# Hank2.net
KiCad netlist of a schematic drawn in EAGLE
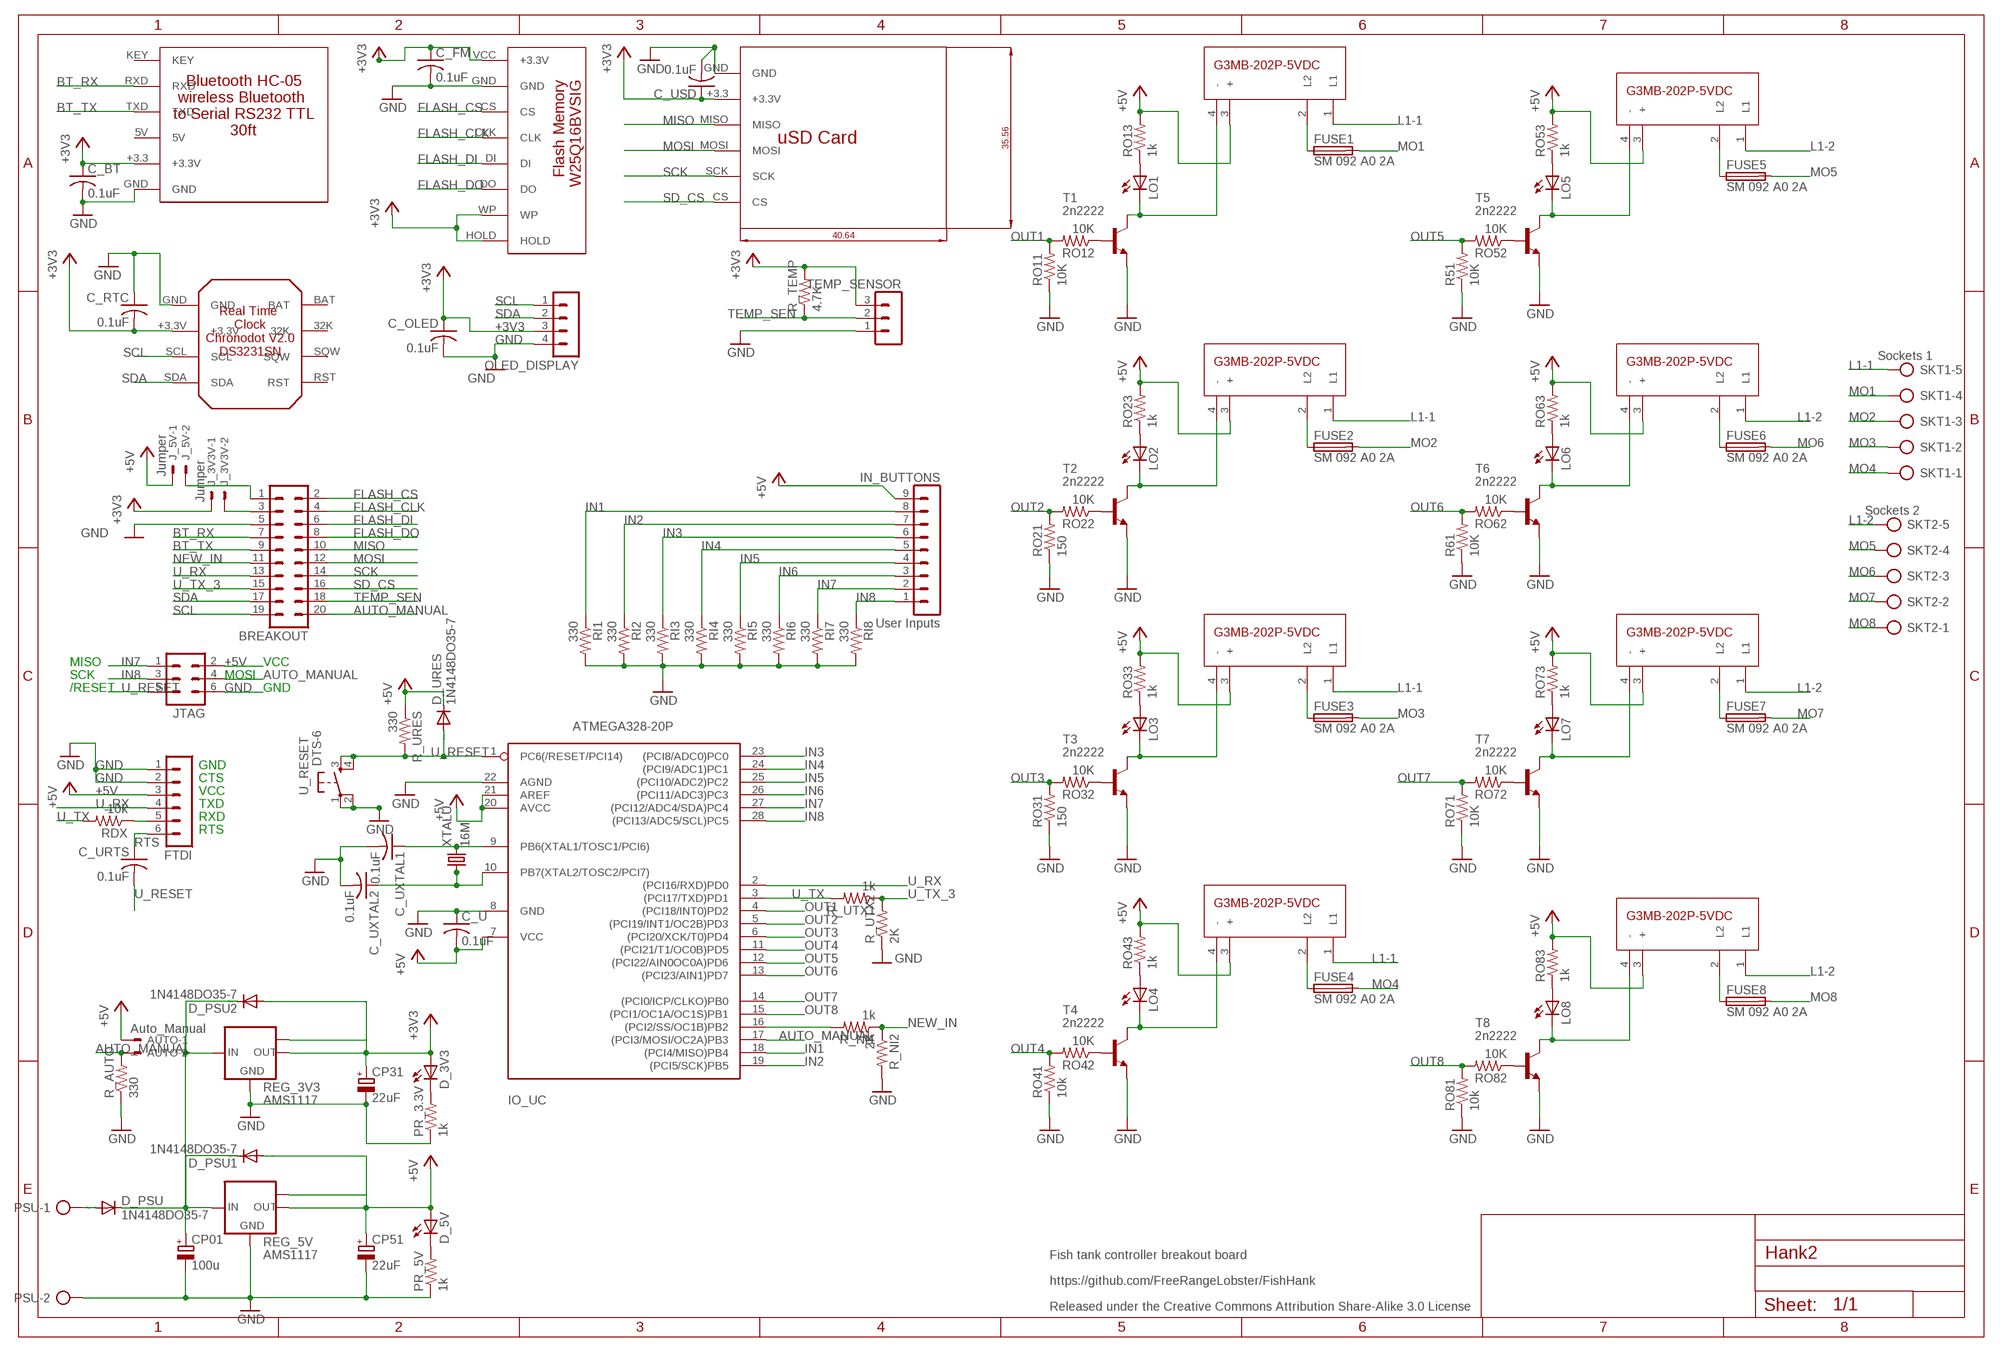
[diagram p0: schematic, sheet 1]

(export (version "E")
  (design (tool "Eeschema 10.0.6"))
  (components
    (comp (ref "AUTO")
      (value "Auto_Manual")
      (footprint "eagle-import:22-23-2021")
      (fields (field (name "MF") "MOLEX") (field (name "MPN") "22-23-2021"))
      (libsource (lib "eagle-import") (part "22-23-2021"))
    )
    (comp (ref "BREAKOUT")
      (value "MA10-2")
      (footprint "eagle-import:MA10-2")
      (libsource (lib "eagle-import") (part "MA10-2"))
    )
    (comp (ref "CP01")
      (value "100u")
      (footprint "eagle-import:E2,5-6")
      (libsource (lib "eagle-import") (part "CPOL-EUE2.5-6"))
    )
    (comp (ref "CP31")
      (value "22uF")
      (footprint "eagle-import:E2,5-6")
      (libsource (lib "eagle-import") (part "CPOL-EUE2.5-6"))
    )
    (comp (ref "CP51")
      (value "22uF")
      (footprint "eagle-import:E2,5-6")
      (libsource (lib "eagle-import") (part "CPOL-EUE2.5-6"))
    )
    (comp (ref "C_BT")
      (value "0.1uF")
      (footprint "eagle-import:C025-024X044")
      (libsource (lib "eagle-import") (part "C-US025-024X044"))
    )
    (comp (ref "C_FM")
      (value "0.1uF")
      (footprint "eagle-import:C025-024X044")
      (libsource (lib "eagle-import") (part "C-US025-024X044"))
    )
    (comp (ref "C_OLED")
      (value "0.1uF")
      (footprint "eagle-import:C025-024X044")
      (libsource (lib "eagle-import") (part "C-US025-024X044"))
    )
    (comp (ref "C_RTC")
      (value "0.1uF")
      (footprint "eagle-import:C025-024X044")
      (libsource (lib "eagle-import") (part "C-US025-024X044"))
    )
    (comp (ref "C_U")
      (value "0.1uF")
      (footprint "eagle-import:C025-024X044")
      (libsource (lib "eagle-import") (part "C-US025-024X044"))
    )
    (comp (ref "C_URTS")
      (value "0.1uF")
      (footprint "eagle-import:C025-024X044")
      (libsource (lib "eagle-import") (part "C-US025-024X044"))
    )
    (comp (ref "C_USD")
      (value "0.1uF")
      (footprint "eagle-import:C025-024X044")
      (libsource (lib "eagle-import") (part "C-US025-024X044"))
    )
    (comp (ref "C_UXTAL1")
      (value "0.1uF")
      (footprint "eagle-import:C025-024X044")
      (libsource (lib "eagle-import") (part "C-US025-024X044"))
    )
    (comp (ref "C_UXTAL2")
      (value "0.1uF")
      (footprint "eagle-import:C025-024X044")
      (libsource (lib "eagle-import") (part "C-US025-024X044"))
    )
    (comp (ref "D_3V3")
      (value "LED3MM")
      (footprint "eagle-import:LED3MM")
      (libsource (lib "eagle-import") (part "LED3MM"))
    )
    (comp (ref "D_5V")
      (value "LED3MM")
      (footprint "eagle-import:LED3MM")
      (libsource (lib "eagle-import") (part "LED3MM"))
    )
    (comp (ref "D_PSU")
      (value "1N4148DO35-7")
      (footprint "eagle-import:DO35-7")
      (libsource (lib "eagle-import") (part "1N4148DO35-7"))
    )
    (comp (ref "D_PSU1")
      (value "1N4148DO35-7")
      (footprint "eagle-import:DO35-7")
      (libsource (lib "eagle-import") (part "1N4148DO35-7"))
    )
    (comp (ref "D_PSU2")
      (value "1N4148DO35-7")
      (footprint "eagle-import:DO35-7")
      (libsource (lib "eagle-import") (part "1N4148DO35-7"))
    )
    (comp (ref "D_URES")
      (value "1N4148DO35-7")
      (footprint "eagle-import:DO35-7")
      (libsource (lib "eagle-import") (part "1N4148DO35-7"))
    )
    (comp (ref "FTDI")
      (value "MA06-1")
      (footprint "eagle-import:MA06-1")
      (libsource (lib "eagle-import") (part "MA06-1"))
    )
    (comp (ref "FUSE1")
      (value "SM 092 A0 2A")
      (footprint "eagle-import:PICOFUSE")
      (libsource (lib "eagle-import") (part "FUSEPICOFUSE"))
    )
    (comp (ref "FUSE2")
      (value "SM 092 A0 2A")
      (footprint "eagle-import:PICOFUSE")
      (libsource (lib "eagle-import") (part "FUSEPICOFUSE"))
    )
    (comp (ref "FUSE3")
      (value "SM 092 A0 2A")
      (footprint "eagle-import:PICOFUSE")
      (libsource (lib "eagle-import") (part "FUSEPICOFUSE"))
    )
    (comp (ref "FUSE4")
      (value "SM 092 A0 2A")
      (footprint "eagle-import:PICOFUSE")
      (libsource (lib "eagle-import") (part "FUSEPICOFUSE"))
    )
    (comp (ref "FUSE5")
      (value "SM 092 A0 2A")
      (footprint "eagle-import:PICOFUSE")
      (libsource (lib "eagle-import") (part "FUSEPICOFUSE"))
    )
    (comp (ref "FUSE6")
      (value "SM 092 A0 2A")
      (footprint "eagle-import:PICOFUSE")
      (libsource (lib "eagle-import") (part "FUSEPICOFUSE"))
    )
    (comp (ref "FUSE7")
      (value "SM 092 A0 2A")
      (footprint "eagle-import:PICOFUSE")
      (libsource (lib "eagle-import") (part "FUSEPICOFUSE"))
    )
    (comp (ref "FUSE8")
      (value "SM 092 A0 2A")
      (footprint "eagle-import:PICOFUSE")
      (libsource (lib "eagle-import") (part "FUSEPICOFUSE"))
    )
    (comp (ref "IN_BUTTONS")
      (value "User Inputs")
      (footprint "eagle-import:MA09-1")
      (libsource (lib "eagle-import") (part "MA09-1"))
    )
    (comp (ref "IO_UC")
      (value "ATMEGA328-20P")
      (footprint "eagle-import:DIL28-3")
      (libsource (lib "eagle-import") (part "ATMEGA328P-20"))
    )
    (comp (ref "JTAG")
      (value "MA03-2")
      (footprint "eagle-import:MA03-2")
      (libsource (lib "eagle-import") (part "MA03-2"))
    )
    (comp (ref "J_3V3V")
      (value "Jumper")
      (footprint "eagle-import:22-23-2021")
      (fields (field (name "MF") "MOLEX") (field (name "MPN") "22-23-2021"))
      (libsource (lib "eagle-import") (part "22-23-2021"))
    )
    (comp (ref "J_5V")
      (value "Jumper")
      (footprint "eagle-import:22-23-2021")
      (fields (field (name "MF") "MOLEX") (field (name "MPN") "22-23-2021"))
      (libsource (lib "eagle-import") (part "22-23-2021"))
    )
    (comp (ref "LO1")
      (value "LED3MM")
      (footprint "eagle-import:LED3MM")
      (libsource (lib "eagle-import") (part "LED3MM"))
    )
    (comp (ref "LO2")
      (value "LED3MM")
      (footprint "eagle-import:LED3MM")
      (libsource (lib "eagle-import") (part "LED3MM"))
    )
    (comp (ref "LO3")
      (value "LED3MM")
      (footprint "eagle-import:LED3MM")
      (libsource (lib "eagle-import") (part "LED3MM"))
    )
    (comp (ref "LO4")
      (value "LED3MM")
      (footprint "eagle-import:LED3MM")
      (libsource (lib "eagle-import") (part "LED3MM"))
    )
    (comp (ref "LO5")
      (value "LED3MM")
      (footprint "eagle-import:LED3MM")
      (libsource (lib "eagle-import") (part "LED3MM"))
    )
    (comp (ref "LO6")
      (value "LED3MM")
      (footprint "eagle-import:LED3MM")
      (libsource (lib "eagle-import") (part "LED3MM"))
    )
    (comp (ref "LO7")
      (value "LED3MM")
      (footprint "eagle-import:LED3MM")
      (libsource (lib "eagle-import") (part "LED3MM"))
    )
    (comp (ref "LO8")
      (value "LED3MM")
      (footprint "eagle-import:LED3MM")
      (libsource (lib "eagle-import") (part "LED3MM"))
    )
    (comp (ref "OLED_DISPLAY")
      (value "MA04-1")
      (footprint "eagle-import:MA04-1")
      (libsource (lib "eagle-import") (part "MA04-1"))
    )
    (comp (ref "PR_3.3V")
      (value "1k")
      (footprint "eagle-import:0207_10")
      (libsource (lib "eagle-import") (part "R-US_0207/10"))
    )
    (comp (ref "PR_5V")
      (value "1k")
      (footprint "eagle-import:0207_10")
      (libsource (lib "eagle-import") (part "R-US_0207/10"))
    )
    (comp (ref "PSU")
      (value "AK500/2")
      (footprint "eagle-import:AK500_2")
      (libsource (lib "eagle-import") (part "AK500/2"))
    )
    (comp (ref "R51")
      (value "10K")
      (footprint "eagle-import:0207_10")
      (libsource (lib "eagle-import") (part "R-US_0207/10"))
    )
    (comp (ref "R61")
      (value "10K")
      (footprint "eagle-import:0207_10")
      (libsource (lib "eagle-import") (part "R-US_0207/10"))
    )
    (comp (ref "RDX")
      (value "10k")
      (footprint "eagle-import:0207_10")
      (libsource (lib "eagle-import") (part "R-US_0207/10"))
    )
    (comp (ref "REG_3V3")
      (value "AMS1117")
      (footprint "eagle-import:SOT223")
      (libsource (lib "eagle-import") (part "AMS1117"))
    )
    (comp (ref "REG_5V")
      (value "AMS1117")
      (footprint "eagle-import:SOT223")
      (libsource (lib "eagle-import") (part "AMS1117"))
    )
    (comp (ref "RI1")
      (value "330")
      (footprint "eagle-import:0207_10")
      (libsource (lib "eagle-import") (part "R-US_0207/10"))
    )
    (comp (ref "RI2")
      (value "330")
      (footprint "eagle-import:0207_10")
      (libsource (lib "eagle-import") (part "R-US_0207/10"))
    )
    (comp (ref "RI3")
      (value "330")
      (footprint "eagle-import:0207_10")
      (libsource (lib "eagle-import") (part "R-US_0207/10"))
    )
    (comp (ref "RI4")
      (value "330")
      (footprint "eagle-import:0207_10")
      (libsource (lib "eagle-import") (part "R-US_0207/10"))
    )
    (comp (ref "RI5")
      (value "330")
      (footprint "eagle-import:0207_10")
      (libsource (lib "eagle-import") (part "R-US_0207/10"))
    )
    (comp (ref "RI6")
      (value "330")
      (footprint "eagle-import:0207_10")
      (libsource (lib "eagle-import") (part "R-US_0207/10"))
    )
    (comp (ref "RI7")
      (value "330")
      (footprint "eagle-import:0207_10")
      (libsource (lib "eagle-import") (part "R-US_0207/10"))
    )
    (comp (ref "RI8")
      (value "330")
      (footprint "eagle-import:0207_10")
      (libsource (lib "eagle-import") (part "R-US_0207/10"))
    )
    (comp (ref "RO11")
      (value "10K")
      (footprint "eagle-import:0207_10")
      (libsource (lib "eagle-import") (part "R-US_0207/10"))
    )
    (comp (ref "RO12")
      (value "10K")
      (footprint "eagle-import:0207_10")
      (libsource (lib "eagle-import") (part "R-US_0207/10"))
    )
    (comp (ref "RO13")
      (value "1k")
      (footprint "eagle-import:0207_10")
      (libsource (lib "eagle-import") (part "R-US_0207/10"))
    )
    (comp (ref "RO21")
      (value "150")
      (footprint "eagle-import:0207_10")
      (libsource (lib "eagle-import") (part "R-US_0207/10"))
    )
    (comp (ref "RO22")
      (value "10K")
      (footprint "eagle-import:0207_10")
      (libsource (lib "eagle-import") (part "R-US_0207/10"))
    )
    (comp (ref "RO23")
      (value "1k")
      (footprint "eagle-import:0207_10")
      (libsource (lib "eagle-import") (part "R-US_0207/10"))
    )
    (comp (ref "RO31")
      (value "150")
      (footprint "eagle-import:0207_10")
      (libsource (lib "eagle-import") (part "R-US_0207/10"))
    )
    (comp (ref "RO32")
      (value "10K")
      (footprint "eagle-import:0207_10")
      (libsource (lib "eagle-import") (part "R-US_0207/10"))
    )
    (comp (ref "RO33")
      (value "1k")
      (footprint "eagle-import:0207_10")
      (libsource (lib "eagle-import") (part "R-US_0207/10"))
    )
    (comp (ref "RO41")
      (value "10k")
      (footprint "eagle-import:0207_10")
      (libsource (lib "eagle-import") (part "R-US_0207/10"))
    )
    (comp (ref "RO42")
      (value "10K")
      (footprint "eagle-import:0207_10")
      (libsource (lib "eagle-import") (part "R-US_0207/10"))
    )
    (comp (ref "RO43")
      (value "1k")
      (footprint "eagle-import:0207_10")
      (libsource (lib "eagle-import") (part "R-US_0207/10"))
    )
    (comp (ref "RO52")
      (value "10K")
      (footprint "eagle-import:0207_10")
      (libsource (lib "eagle-import") (part "R-US_0207/10"))
    )
    (comp (ref "RO53")
      (value "1k")
      (footprint "eagle-import:0207_10")
      (libsource (lib "eagle-import") (part "R-US_0207/10"))
    )
    (comp (ref "RO62")
      (value "10K")
      (footprint "eagle-import:0207_10")
      (libsource (lib "eagle-import") (part "R-US_0207/10"))
    )
    (comp (ref "RO63")
      (value "1k")
      (footprint "eagle-import:0207_10")
      (libsource (lib "eagle-import") (part "R-US_0207/10"))
    )
    (comp (ref "RO71")
      (value "10K")
      (footprint "eagle-import:0207_10")
      (libsource (lib "eagle-import") (part "R-US_0207/10"))
    )
    (comp (ref "RO72")
      (value "10K")
      (footprint "eagle-import:0207_10")
      (libsource (lib "eagle-import") (part "R-US_0207/10"))
    )
    (comp (ref "RO73")
      (value "1k")
      (footprint "eagle-import:0207_10")
      (libsource (lib "eagle-import") (part "R-US_0207/10"))
    )
    (comp (ref "RO81")
      (value "10k")
      (footprint "eagle-import:0207_10")
      (libsource (lib "eagle-import") (part "R-US_0207/10"))
    )
    (comp (ref "RO82")
      (value "10K")
      (footprint "eagle-import:0207_10")
      (libsource (lib "eagle-import") (part "R-US_0207/10"))
    )
    (comp (ref "RO83")
      (value "1k")
      (footprint "eagle-import:0207_10")
      (libsource (lib "eagle-import") (part "R-US_0207/10"))
    )
    (comp (ref "R_AUTO")
      (value "330")
      (footprint "eagle-import:0207_10")
      (libsource (lib "eagle-import") (part "R-US_0207/10"))
    )
    (comp (ref "R_NI1")
      (value "1k")
      (footprint "eagle-import:0207_10")
      (libsource (lib "eagle-import") (part "R-US_0207/10"))
    )
    (comp (ref "R_NI2")
      (value "2K")
      (footprint "eagle-import:0207_10")
      (libsource (lib "eagle-import") (part "R-US_0207/10"))
    )
    (comp (ref "R_TEMP")
      (value "4.7K")
      (footprint "eagle-import:0207_10")
      (libsource (lib "eagle-import") (part "R-US_0207/10"))
    )
    (comp (ref "R_URES")
      (value "330")
      (footprint "eagle-import:0207_10")
      (libsource (lib "eagle-import") (part "R-US_0207/10"))
    )
    (comp (ref "R_UTX1")
      (value "1k")
      (footprint "eagle-import:0207_10")
      (libsource (lib "eagle-import") (part "R-US_0207/10"))
    )
    (comp (ref "R_UTX2")
      (value "2K")
      (footprint "eagle-import:0207_10")
      (libsource (lib "eagle-import") (part "R-US_0207/10"))
    )
    (comp (ref "SKT1")
      (value "Sockets 1")
      (footprint "eagle-import:AK500_5")
      (libsource (lib "eagle-import") (part "AK500/5"))
    )
    (comp (ref "SKT2")
      (value "Sockets 2")
      (footprint "eagle-import:AK500_5")
      (libsource (lib "eagle-import") (part "AK500/5"))
    )
    (comp (ref "SSR1")
      (value "SSR")
      (footprint "eagle-import:SSR_FOOTPRINT")
      (libsource (lib "eagle-import") (part "SSR"))
    )
    (comp (ref "SSR2")
      (value "SSR")
      (footprint "eagle-import:SSR_FOOTPRINT")
      (libsource (lib "eagle-import") (part "SSR"))
    )
    (comp (ref "SSR3")
      (value "SSR")
      (footprint "eagle-import:SSR_FOOTPRINT")
      (libsource (lib "eagle-import") (part "SSR"))
    )
    (comp (ref "SSR4")
      (value "SSR")
      (footprint "eagle-import:SSR_FOOTPRINT")
      (libsource (lib "eagle-import") (part "SSR"))
    )
    (comp (ref "SSR5")
      (value "SSR")
      (footprint "eagle-import:SSR_FOOTPRINT")
      (libsource (lib "eagle-import") (part "SSR"))
    )
    (comp (ref "SSR6")
      (value "SSR")
      (footprint "eagle-import:SSR_FOOTPRINT")
      (libsource (lib "eagle-import") (part "SSR"))
    )
    (comp (ref "SSR7")
      (value "SSR")
      (footprint "eagle-import:SSR_FOOTPRINT")
      (libsource (lib "eagle-import") (part "SSR"))
    )
    (comp (ref "SSR8")
      (value "SSR")
      (footprint "eagle-import:SSR_FOOTPRINT")
      (libsource (lib "eagle-import") (part "SSR"))
    )
    (comp (ref "T1")
      (value "2n2222")
      (footprint "eagle-import:TO92-ECB")
      (libsource (lib "eagle-import") (part "2SC458"))
    )
    (comp (ref "T2")
      (value "2n2222")
      (footprint "eagle-import:TO92-ECB")
      (libsource (lib "eagle-import") (part "2SC458"))
    )
    (comp (ref "T3")
      (value "2n2222")
      (footprint "eagle-import:TO92-ECB")
      (libsource (lib "eagle-import") (part "2SC458"))
    )
    (comp (ref "T4")
      (value "2n2222")
      (footprint "eagle-import:TO92-ECB")
      (libsource (lib "eagle-import") (part "2SC458"))
    )
    (comp (ref "T5")
      (value "2n2222")
      (footprint "eagle-import:TO92-ECB")
      (libsource (lib "eagle-import") (part "2SC458"))
    )
    (comp (ref "T6")
      (value "2n2222")
      (footprint "eagle-import:TO92-ECB")
      (libsource (lib "eagle-import") (part "2SC458"))
    )
    (comp (ref "T7")
      (value "2n2222")
      (footprint "eagle-import:TO92-ECB")
      (libsource (lib "eagle-import") (part "2SC458"))
    )
    (comp (ref "T8")
      (value "2n2222")
      (footprint "eagle-import:TO92-ECB")
      (libsource (lib "eagle-import") (part "2SC458"))
    )
    (comp (ref "TEMP_SENSOR")
      (value "MA03-1")
      (footprint "eagle-import:MA03-1")
      (libsource (lib "eagle-import") (part "MA03-1"))
    )
    (comp (ref "U$1")
      (value "FLASH_MEMORY")
      (footprint "eagle-import:FLASHMEMORY_FOOTPRINT")
      (libsource (lib "eagle-import") (part "FLASH_MEMORY"))
    )
    (comp (ref "U$4")
      (value "BLUETOOTH")
      (footprint "eagle-import:BLUETOOTH_FOOTPRINT")
      (libsource (lib "eagle-import") (part "BLUETOOTH"))
    )
    (comp (ref "U$6")
      (value "RTC")
      (footprint "eagle-import:RTC_FOOTPRINT")
      (libsource (lib "eagle-import") (part "RTC"))
    )
    (comp (ref "U$7")
      (value "SD_CARD_READER")
      (footprint "eagle-import:SD_CARD_READER_FOOTPRINT")
      (libsource (lib "eagle-import") (part "SD_CARD_READER"))
    )
    (comp (ref "U_RESET")
      (value "DTS-6")
      (footprint "eagle-import:DTS-6")
      (libsource (lib "eagle-import") (part "DTS-6"))
    )
    (comp (ref "XTALU")
      (value "16M")
      (footprint "eagle-import:HC49_S")
      (libsource (lib "eagle-import") (part "CRYSTALHC49S"))
    )
  )
  (nets
    (net (code "1") (name "+3V3") (class "Default")
      (node (ref "CP31") (pin "+") (pinfunction "+_+") (pintype "passive"))
      (node (ref "C_BT") (pin "1") (pinfunction "1_1") (pintype "passive"))
      (node (ref "C_FM") (pin "1") (pinfunction "1_1") (pintype "passive"))
      (node (ref "C_OLED") (pin "1") (pinfunction "1_1") (pintype "passive"))
      (node (ref "C_RTC") (pin "2") (pinfunction "2_2") (pintype "passive"))
      (node (ref "C_USD") (pin "1") (pinfunction "1_1") (pintype "passive"))
      (node (ref "D_3V3") (pin "A") (pinfunction "A_A") (pintype "passive"))
      (node (ref "D_PSU2") (pin "A") (pinfunction "A_A") (pintype "passive"))
      (node (ref "J_3V3V") (pin "1") (pinfunction "S_1") (pintype "passive"))
      (node (ref "OLED_DISPLAY") (pin "3") (pinfunction "3_3") (pintype "passive"))
      (node (ref "REG_3V3") (pin "2") (pinfunction "OUT_2") (pintype "passive"))
      (node (ref "REG_3V3") (pin "TAB") (pinfunction "OUT1_TAB") (pintype "passive"))
      (node (ref "R_TEMP") (pin "2") (pinfunction "2_2") (pintype "passive"))
      (node (ref "TEMP_SENSOR") (pin "3") (pinfunction "3_3") (pintype "passive"))
      (node (ref "U$1") (pin "HOLD") (pinfunction "HOLD_HOLD") (pintype "bidirectional"))
      (node (ref "U$1") (pin "VCC") (pinfunction "+3.3V_VCC") (pintype "bidirectional"))
      (node (ref "U$1") (pin "WP") (pinfunction "WP_WP") (pintype "bidirectional"))
      (node (ref "U$4") (pin "+3.3") (pinfunction "+3.3V_+3.3") (pintype "bidirectional"))
      (node (ref "U$6") (pin "+3.3V") (pinfunction "+3.3V_+3.3V") (pintype "bidirectional"))
      (node (ref "U$7") (pin "+3.3") (pinfunction "+3.3V_+3.3") (pintype "bidirectional"))
    )
    (net (code "2") (name "+5V") (class "Default")
      (node (ref "AUTO") (pin "1") (pinfunction "S_1") (pintype "passive"))
      (node (ref "CP51") (pin "+") (pinfunction "+_+") (pintype "passive"))
      (node (ref "C_U") (pin "2") (pinfunction "2_2") (pintype "passive"))
      (node (ref "D_5V") (pin "A") (pinfunction "A_A") (pintype "passive"))
      (node (ref "D_PSU1") (pin "A") (pinfunction "A_A") (pintype "passive"))
      (node (ref "D_URES") (pin "C") (pinfunction "C_C") (pintype "passive"))
      (node (ref "FTDI") (pin "3") (pinfunction "3_3") (pintype "passive"))
      (node (ref "IN_BUTTONS") (pin "9") (pinfunction "9_9") (pintype "passive"))
      (node (ref "IO_UC") (pin "20") (pinfunction "AVCC_20") (pintype "bidirectional"))
      (node (ref "IO_UC") (pin "21") (pinfunction "AREF_21") (pintype "bidirectional"))
      (node (ref "IO_UC") (pin "7") (pinfunction "VCC_7") (pintype "bidirectional"))
      (node (ref "JTAG") (pin "2") (pinfunction "2_2") (pintype "passive"))
      (node (ref "J_5V") (pin "1") (pinfunction "S_1") (pintype "passive"))
      (node (ref "REG_5V") (pin "2") (pinfunction "OUT_2") (pintype "passive"))
      (node (ref "REG_5V") (pin "TAB") (pinfunction "OUT1_TAB") (pintype "passive"))
      (node (ref "RO13") (pin "2") (pinfunction "2_2") (pintype "passive"))
      (node (ref "RO23") (pin "2") (pinfunction "2_2") (pintype "passive"))
      (node (ref "RO33") (pin "2") (pinfunction "2_2") (pintype "passive"))
      (node (ref "RO43") (pin "2") (pinfunction "2_2") (pintype "passive"))
      (node (ref "RO53") (pin "2") (pinfunction "2_2") (pintype "passive"))
      (node (ref "RO63") (pin "2") (pinfunction "2_2") (pintype "passive"))
      (node (ref "RO73") (pin "2") (pinfunction "2_2") (pintype "passive"))
      (node (ref "RO83") (pin "2") (pinfunction "2_2") (pintype "passive"))
      (node (ref "R_URES") (pin "1") (pinfunction "1_1") (pintype "passive"))
      (node (ref "SSR1") (pin "3") (pinfunction "+_3") (pintype "bidirectional"))
      (node (ref "SSR2") (pin "3") (pinfunction "+_3") (pintype "bidirectional"))
      (node (ref "SSR3") (pin "3") (pinfunction "+_3") (pintype "bidirectional"))
      (node (ref "SSR4") (pin "3") (pinfunction "+_3") (pintype "bidirectional"))
      (node (ref "SSR5") (pin "3") (pinfunction "+_3") (pintype "bidirectional"))
      (node (ref "SSR6") (pin "3") (pinfunction "+_3") (pintype "bidirectional"))
      (node (ref "SSR7") (pin "3") (pinfunction "+_3") (pintype "bidirectional"))
      (node (ref "SSR8") (pin "3") (pinfunction "+_3") (pintype "bidirectional"))
    )
    (net (code "3") (name "/AUTO_MANUAL") (class "Default")
      (node (ref "AUTO") (pin "2") (pinfunction "S_2") (pintype "passive"))
      (node (ref "BREAKOUT") (pin "20") (pinfunction "20_20") (pintype "passive"))
      (node (ref "IO_UC") (pin "17") (pinfunction "(PCI3/MOSI/OC2A)PB3_17") (pintype "bidirectional"))
      (node (ref "JTAG") (pin "4") (pinfunction "4_4") (pintype "passive"))
      (node (ref "R_AUTO") (pin "2") (pinfunction "2_2") (pintype "passive"))
    )
    (net (code "4") (name "/BT_RX") (class "Default")
      (node (ref "BREAKOUT") (pin "7") (pinfunction "7_7") (pintype "passive"))
      (node (ref "U$4") (pin "RXD") (pinfunction "RXD_RXD") (pintype "bidirectional"))
    )
    (net (code "5") (name "/BT_TX") (class "Default")
      (node (ref "BREAKOUT") (pin "9") (pinfunction "9_9") (pintype "passive"))
      (node (ref "U$4") (pin "TXD") (pinfunction "TXD_TXD") (pintype "bidirectional"))
    )
    (net (code "6") (name "/FLASH_CLK") (class "Default")
      (node (ref "BREAKOUT") (pin "4") (pinfunction "4_4") (pintype "passive"))
      (node (ref "U$1") (pin "CLK") (pinfunction "CLK_CLK") (pintype "bidirectional"))
    )
    (net (code "7") (name "/FLASH_CS") (class "Default")
      (node (ref "BREAKOUT") (pin "2") (pinfunction "2_2") (pintype "passive"))
      (node (ref "U$1") (pin "CS") (pinfunction "CS_CS") (pintype "bidirectional"))
    )
    (net (code "8") (name "/FLASH_DI") (class "Default")
      (node (ref "BREAKOUT") (pin "6") (pinfunction "6_6") (pintype "passive"))
      (node (ref "U$1") (pin "DI") (pinfunction "DI_DI") (pintype "bidirectional"))
    )
    (net (code "9") (name "/FLASH_DO") (class "Default")
      (node (ref "BREAKOUT") (pin "8") (pinfunction "8_8") (pintype "passive"))
      (node (ref "U$1") (pin "DO") (pinfunction "DO_DO") (pintype "bidirectional"))
    )
    (net (code "10") (name "/IN1") (class "Default")
      (node (ref "IN_BUTTONS") (pin "8") (pinfunction "8_8") (pintype "passive"))
      (node (ref "IO_UC") (pin "18") (pinfunction "(PCI4/MISO)PB4_18") (pintype "bidirectional"))
      (node (ref "RI1") (pin "1") (pinfunction "1_1") (pintype "passive"))
    )
    (net (code "11") (name "/IN2") (class "Default")
      (node (ref "IN_BUTTONS") (pin "7") (pinfunction "7_7") (pintype "passive"))
      (node (ref "IO_UC") (pin "19") (pinfunction "(PCI5/SCK)PB5_19") (pintype "bidirectional"))
      (node (ref "RI2") (pin "1") (pinfunction "1_1") (pintype "passive"))
    )
    (net (code "12") (name "/IN3") (class "Default")
      (node (ref "IN_BUTTONS") (pin "6") (pinfunction "6_6") (pintype "passive"))
      (node (ref "IO_UC") (pin "23") (pinfunction "(PCI8/ADC0)PC0_23") (pintype "bidirectional"))
      (node (ref "RI3") (pin "1") (pinfunction "1_1") (pintype "passive"))
    )
    (net (code "13") (name "/IN4") (class "Default")
      (node (ref "IN_BUTTONS") (pin "5") (pinfunction "5_5") (pintype "passive"))
      (node (ref "IO_UC") (pin "24") (pinfunction "(PCI9/ADC1)PC1_24") (pintype "bidirectional"))
      (node (ref "RI4") (pin "1") (pinfunction "1_1") (pintype "passive"))
    )
    (net (code "14") (name "/IN5") (class "Default")
      (node (ref "IN_BUTTONS") (pin "4") (pinfunction "4_4") (pintype "passive"))
      (node (ref "IO_UC") (pin "25") (pinfunction "(PCI10/ADC2)PC2_25") (pintype "bidirectional"))
      (node (ref "RI5") (pin "1") (pinfunction "1_1") (pintype "passive"))
    )
    (net (code "15") (name "/IN6") (class "Default")
      (node (ref "IN_BUTTONS") (pin "3") (pinfunction "3_3") (pintype "passive"))
      (node (ref "IO_UC") (pin "26") (pinfunction "(PCI11/ADC3)PC3_26") (pintype "bidirectional"))
      (node (ref "RI6") (pin "1") (pinfunction "1_1") (pintype "passive"))
    )
    (net (code "16") (name "/IN7") (class "Default")
      (node (ref "IN_BUTTONS") (pin "2") (pinfunction "2_2") (pintype "passive"))
      (node (ref "IO_UC") (pin "27") (pinfunction "(PCI12/ADC4/SDA)PC4_27") (pintype "bidirectional"))
      (node (ref "JTAG") (pin "1") (pinfunction "1_1") (pintype "passive"))
      (node (ref "RI7") (pin "1") (pinfunction "1_1") (pintype "passive"))
    )
    (net (code "17") (name "/IN8") (class "Default")
      (node (ref "IN_BUTTONS") (pin "1") (pinfunction "1_1") (pintype "passive"))
      (node (ref "IO_UC") (pin "28") (pinfunction "(PCI13/ADC5/SCL)PC5_28") (pintype "bidirectional"))
      (node (ref "JTAG") (pin "3") (pinfunction "3_3") (pintype "passive"))
      (node (ref "RI8") (pin "1") (pinfunction "1_1") (pintype "passive"))
    )
    (net (code "18") (name "/L1-1") (class "Default")
      (node (ref "SKT1") (pin "5") (pinfunction "KL_5") (pintype "passive"))
      (node (ref "SSR1") (pin "1") (pinfunction "L1_1") (pintype "bidirectional"))
      (node (ref "SSR2") (pin "1") (pinfunction "L1_1") (pintype "bidirectional"))
      (node (ref "SSR3") (pin "1") (pinfunction "L1_1") (pintype "bidirectional"))
      (node (ref "SSR4") (pin "1") (pinfunction "L1_1") (pintype "bidirectional"))
    )
    (net (code "19") (name "/L1-2") (class "Default")
      (node (ref "SKT2") (pin "5") (pinfunction "KL_5") (pintype "passive"))
      (node (ref "SSR5") (pin "1") (pinfunction "L1_1") (pintype "bidirectional"))
      (node (ref "SSR6") (pin "1") (pinfunction "L1_1") (pintype "bidirectional"))
      (node (ref "SSR7") (pin "1") (pinfunction "L1_1") (pintype "bidirectional"))
      (node (ref "SSR8") (pin "1") (pinfunction "L1_1") (pintype "bidirectional"))
    )
    (net (code "20") (name "/MISO") (class "Default")
      (node (ref "BREAKOUT") (pin "10") (pinfunction "10_10") (pintype "passive"))
      (node (ref "U$7") (pin "MISO") (pinfunction "MISO_MISO") (pintype "bidirectional"))
    )
    (net (code "21") (name "/MO1") (class "Default")
      (node (ref "FUSE1") (pin "2") (pinfunction "2_2") (pintype "passive"))
      (node (ref "SKT1") (pin "4") (pinfunction "KL_4") (pintype "passive"))
    )
    (net (code "22") (name "/MO2") (class "Default")
      (node (ref "FUSE2") (pin "2") (pinfunction "2_2") (pintype "passive"))
      (node (ref "SKT1") (pin "3") (pinfunction "KL_3") (pintype "passive"))
    )
    (net (code "23") (name "/MO3") (class "Default")
      (node (ref "FUSE3") (pin "2") (pinfunction "2_2") (pintype "passive"))
      (node (ref "SKT1") (pin "2") (pinfunction "KL_2") (pintype "passive"))
    )
    (net (code "24") (name "/MO4") (class "Default")
      (node (ref "FUSE4") (pin "2") (pinfunction "2_2") (pintype "passive"))
      (node (ref "SKT1") (pin "1") (pinfunction "KL_1") (pintype "passive"))
    )
    (net (code "25") (name "/MO5") (class "Default")
      (node (ref "FUSE5") (pin "2") (pinfunction "2_2") (pintype "passive"))
      (node (ref "SKT2") (pin "4") (pinfunction "KL_4") (pintype "passive"))
    )
    (net (code "26") (name "/MO6") (class "Default")
      (node (ref "FUSE6") (pin "2") (pinfunction "2_2") (pintype "passive"))
      (node (ref "SKT2") (pin "3") (pinfunction "KL_3") (pintype "passive"))
    )
    (net (code "27") (name "/MO7") (class "Default")
      (node (ref "FUSE7") (pin "2") (pinfunction "2_2") (pintype "passive"))
      (node (ref "SKT2") (pin "2") (pinfunction "KL_2") (pintype "passive"))
    )
    (net (code "28") (name "/MO8") (class "Default")
      (node (ref "FUSE8") (pin "2") (pinfunction "2_2") (pintype "passive"))
      (node (ref "SKT2") (pin "1") (pinfunction "KL_1") (pintype "passive"))
    )
    (net (code "29") (name "/MOSI") (class "Default")
      (node (ref "BREAKOUT") (pin "12") (pinfunction "12_12") (pintype "passive"))
      (node (ref "U$7") (pin "MOSI") (pinfunction "MOSI_MOSI") (pintype "bidirectional"))
    )
    (net (code "30") (name "/NEW_IN") (class "Default")
      (node (ref "BREAKOUT") (pin "11") (pinfunction "11_11") (pintype "passive"))
      (node (ref "R_NI1") (pin "1") (pinfunction "1_1") (pintype "passive"))
      (node (ref "R_NI2") (pin "1") (pinfunction "1_1") (pintype "passive"))
    )
    (net (code "31") (name "/OUT1") (class "Default")
      (node (ref "IO_UC") (pin "4") (pinfunction "(PCI18/INT0)PD2_4") (pintype "bidirectional"))
      (node (ref "RO11") (pin "2") (pinfunction "2_2") (pintype "passive"))
      (node (ref "RO12") (pin "2") (pinfunction "2_2") (pintype "passive"))
    )
    (net (code "32") (name "/OUT2") (class "Default")
      (node (ref "IO_UC") (pin "5") (pinfunction "(PCI19/INT1/OC2B)PD3_5") (pintype "bidirectional"))
      (node (ref "RO21") (pin "2") (pinfunction "2_2") (pintype "passive"))
      (node (ref "RO22") (pin "2") (pinfunction "2_2") (pintype "passive"))
    )
    (net (code "33") (name "/OUT3") (class "Default")
      (node (ref "IO_UC") (pin "6") (pinfunction "(PCI20/XCK/T0)PD4_6") (pintype "bidirectional"))
      (node (ref "RO31") (pin "2") (pinfunction "2_2") (pintype "passive"))
      (node (ref "RO32") (pin "2") (pinfunction "2_2") (pintype "passive"))
    )
    (net (code "34") (name "/OUT4") (class "Default")
      (node (ref "IO_UC") (pin "11") (pinfunction "(PCI21/T1/OC0B)PD5_11") (pintype "bidirectional"))
      (node (ref "RO41") (pin "2") (pinfunction "2_2") (pintype "passive"))
      (node (ref "RO42") (pin "2") (pinfunction "2_2") (pintype "passive"))
    )
    (net (code "35") (name "/OUT5") (class "Default")
      (node (ref "IO_UC") (pin "12") (pinfunction "(PCI22/AIN0OC0A)PD6_12") (pintype "bidirectional"))
      (node (ref "R51") (pin "2") (pinfunction "2_2") (pintype "passive"))
      (node (ref "RO52") (pin "2") (pinfunction "2_2") (pintype "passive"))
    )
    (net (code "36") (name "/OUT6") (class "Default")
      (node (ref "IO_UC") (pin "13") (pinfunction "(PCI23/AIN1)PD7_13") (pintype "bidirectional"))
      (node (ref "R61") (pin "2") (pinfunction "2_2") (pintype "passive"))
      (node (ref "RO62") (pin "2") (pinfunction "2_2") (pintype "passive"))
    )
    (net (code "37") (name "/OUT7") (class "Default")
      (node (ref "IO_UC") (pin "14") (pinfunction "(PCI0/ICP/CLKO)PB0_14") (pintype "bidirectional"))
      (node (ref "RO71") (pin "2") (pinfunction "2_2") (pintype "passive"))
      (node (ref "RO72") (pin "2") (pinfunction "2_2") (pintype "passive"))
    )
    (net (code "38") (name "/OUT8") (class "Default")
      (node (ref "IO_UC") (pin "15") (pinfunction "(PCI1/OC1A/OC1S)PB1_15") (pintype "bidirectional"))
      (node (ref "RO81") (pin "2") (pinfunction "2_2") (pintype "passive"))
      (node (ref "RO82") (pin "2") (pinfunction "2_2") (pintype "passive"))
    )
    (net (code "39") (name "/RTS") (class "Default")
      (node (ref "C_URTS") (pin "1") (pinfunction "1_1") (pintype "passive"))
      (node (ref "FTDI") (pin "6") (pinfunction "6_6") (pintype "passive"))
    )
    (net (code "40") (name "/SCK") (class "Default")
      (node (ref "BREAKOUT") (pin "14") (pinfunction "14_14") (pintype "passive"))
      (node (ref "U$7") (pin "SCK") (pinfunction "SCK_SCK") (pintype "bidirectional"))
    )
    (net (code "41") (name "/SCL") (class "Default")
      (node (ref "BREAKOUT") (pin "19") (pinfunction "19_19") (pintype "passive"))
      (node (ref "OLED_DISPLAY") (pin "1") (pinfunction "1_1") (pintype "passive"))
      (node (ref "U$6") (pin "SCL") (pinfunction "SCL_SCL") (pintype "bidirectional"))
    )
    (net (code "42") (name "/SDA") (class "Default")
      (node (ref "BREAKOUT") (pin "17") (pinfunction "17_17") (pintype "passive"))
      (node (ref "OLED_DISPLAY") (pin "2") (pinfunction "2_2") (pintype "passive"))
      (node (ref "U$6") (pin "SDA") (pinfunction "SDA_SDA") (pintype "bidirectional"))
    )
    (net (code "43") (name "/SD_CS") (class "Default")
      (node (ref "BREAKOUT") (pin "16") (pinfunction "16_16") (pintype "passive"))
      (node (ref "U$7") (pin "CS") (pinfunction "CS_CS") (pintype "bidirectional"))
    )
    (net (code "44") (name "/TEMP_SEN") (class "Default")
      (node (ref "BREAKOUT") (pin "18") (pinfunction "18_18") (pintype "passive"))
      (node (ref "R_TEMP") (pin "1") (pinfunction "1_1") (pintype "passive"))
      (node (ref "TEMP_SENSOR") (pin "2") (pinfunction "2_2") (pintype "passive"))
    )
    (net (code "45") (name "/U_RESET") (class "Default")
      (node (ref "C_URTS") (pin "2") (pinfunction "2_2") (pintype "passive"))
      (node (ref "D_URES") (pin "A") (pinfunction "A_A") (pintype "passive"))
      (node (ref "IO_UC") (pin "1") (pinfunction "PC6(/RESET/PCI14)_1") (pintype "bidirectional"))
      (node (ref "JTAG") (pin "5") (pinfunction "5_5") (pintype "passive"))
      (node (ref "R_URES") (pin "2") (pinfunction "2_2") (pintype "passive"))
      (node (ref "U_RESET") (pin "3") (pinfunction "3_3") (pintype "passive"))
      (node (ref "U_RESET") (pin "4") (pinfunction "4_4") (pintype "passive"))
    )
    (net (code "46") (name "/U_RX") (class "Default")
      (node (ref "BREAKOUT") (pin "13") (pinfunction "13_13") (pintype "passive"))
      (node (ref "FTDI") (pin "4") (pinfunction "4_4") (pintype "passive"))
      (node (ref "IO_UC") (pin "2") (pinfunction "(PCI16/RXD)PD0_2") (pintype "bidirectional"))
    )
    (net (code "47") (name "/U_TX") (class "Default")
      (node (ref "IO_UC") (pin "3") (pinfunction "(PCI17/TXD)PD1_3") (pintype "bidirectional"))
      (node (ref "RDX") (pin "2") (pinfunction "2_2") (pintype "passive"))
      (node (ref "R_UTX1") (pin "2") (pinfunction "2_2") (pintype "passive"))
    )
    (net (code "48") (name "/U_TX_3") (class "Default")
      (node (ref "BREAKOUT") (pin "15") (pinfunction "15_15") (pintype "passive"))
      (node (ref "R_UTX1") (pin "1") (pinfunction "1_1") (pintype "passive"))
      (node (ref "R_UTX2") (pin "2") (pinfunction "2_2") (pintype "passive"))
    )
    (net (code "49") (name "GND") (class "Default")
      (node (ref "BREAKOUT") (pin "5") (pinfunction "5_5") (pintype "passive"))
      (node (ref "CP01") (pin "-") (pinfunction "-_-") (pintype "passive"))
      (node (ref "CP31") (pin "-") (pinfunction "-_-") (pintype "passive"))
      (node (ref "CP51") (pin "-") (pinfunction "-_-") (pintype "passive"))
      (node (ref "C_BT") (pin "2") (pinfunction "2_2") (pintype "passive"))
      (node (ref "C_FM") (pin "2") (pinfunction "2_2") (pintype "passive"))
      (node (ref "C_OLED") (pin "2") (pinfunction "2_2") (pintype "passive"))
      (node (ref "C_RTC") (pin "1") (pinfunction "1_1") (pintype "passive"))
      (node (ref "C_U") (pin "1") (pinfunction "1_1") (pintype "passive"))
      (node (ref "C_USD") (pin "2") (pinfunction "2_2") (pintype "passive"))
      (node (ref "C_UXTAL1") (pin "2") (pinfunction "2_2") (pintype "passive"))
      (node (ref "C_UXTAL2") (pin "2") (pinfunction "2_2") (pintype "passive"))
      (node (ref "FTDI") (pin "1") (pinfunction "1_1") (pintype "passive"))
      (node (ref "FTDI") (pin "2") (pinfunction "2_2") (pintype "passive"))
      (node (ref "IO_UC") (pin "22") (pinfunction "AGND_22") (pintype "bidirectional"))
      (node (ref "IO_UC") (pin "8") (pinfunction "GND_8") (pintype "bidirectional"))
      (node (ref "JTAG") (pin "6") (pinfunction "6_6") (pintype "passive"))
      (node (ref "OLED_DISPLAY") (pin "4") (pinfunction "4_4") (pintype "passive"))
      (node (ref "PR_3.3V") (pin "1") (pinfunction "1_1") (pintype "passive"))
      (node (ref "PR_5V") (pin "1") (pinfunction "1_1") (pintype "passive"))
      (node (ref "PSU") (pin "2") (pinfunction "KL_2") (pintype "passive"))
      (node (ref "R51") (pin "1") (pinfunction "1_1") (pintype "passive"))
      (node (ref "R61") (pin "1") (pinfunction "1_1") (pintype "passive"))
      (node (ref "REG_3V3") (pin "1") (pinfunction "GND_1") (pintype "input"))
      (node (ref "REG_5V") (pin "1") (pinfunction "GND_1") (pintype "input"))
      (node (ref "RI1") (pin "2") (pinfunction "2_2") (pintype "passive"))
      (node (ref "RI2") (pin "2") (pinfunction "2_2") (pintype "passive"))
      (node (ref "RI3") (pin "2") (pinfunction "2_2") (pintype "passive"))
      (node (ref "RI4") (pin "2") (pinfunction "2_2") (pintype "passive"))
      (node (ref "RI5") (pin "2") (pinfunction "2_2") (pintype "passive"))
      (node (ref "RI6") (pin "2") (pinfunction "2_2") (pintype "passive"))
      (node (ref "RI7") (pin "2") (pinfunction "2_2") (pintype "passive"))
      (node (ref "RI8") (pin "2") (pinfunction "2_2") (pintype "passive"))
      (node (ref "RO11") (pin "1") (pinfunction "1_1") (pintype "passive"))
      (node (ref "RO21") (pin "1") (pinfunction "1_1") (pintype "passive"))
      (node (ref "RO31") (pin "1") (pinfunction "1_1") (pintype "passive"))
      (node (ref "RO41") (pin "1") (pinfunction "1_1") (pintype "passive"))
      (node (ref "RO71") (pin "1") (pinfunction "1_1") (pintype "passive"))
      (node (ref "RO81") (pin "1") (pinfunction "1_1") (pintype "passive"))
      (node (ref "R_AUTO") (pin "1") (pinfunction "1_1") (pintype "passive"))
      (node (ref "R_NI2") (pin "2") (pinfunction "2_2") (pintype "passive"))
      (node (ref "R_UTX2") (pin "1") (pinfunction "1_1") (pintype "passive"))
      (node (ref "T1") (pin "E") (pinfunction "E_E") (pintype "passive"))
      (node (ref "T2") (pin "E") (pinfunction "E_E") (pintype "passive"))
      (node (ref "T3") (pin "E") (pinfunction "E_E") (pintype "passive"))
      (node (ref "T4") (pin "E") (pinfunction "E_E") (pintype "passive"))
      (node (ref "T5") (pin "E") (pinfunction "E_E") (pintype "passive"))
      (node (ref "T6") (pin "E") (pinfunction "E_E") (pintype "passive"))
      (node (ref "T7") (pin "E") (pinfunction "E_E") (pintype "passive"))
      (node (ref "T8") (pin "E") (pinfunction "E_E") (pintype "passive"))
      (node (ref "TEMP_SENSOR") (pin "1") (pinfunction "1_1") (pintype "passive"))
      (node (ref "U$1") (pin "GND") (pinfunction "GND_GND") (pintype "bidirectional"))
      (node (ref "U$4") (pin "GND") (pinfunction "GND_GND") (pintype "bidirectional"))
      (node (ref "U$6") (pin "GND") (pinfunction "GND_GND") (pintype "bidirectional"))
      (node (ref "U$7") (pin "GND") (pinfunction "GND_GND") (pintype "bidirectional"))
      (node (ref "U_RESET") (pin "1") (pinfunction "1_1") (pintype "passive"))
      (node (ref "U_RESET") (pin "2") (pinfunction "2_2") (pintype "passive"))
    )
    (net (code "50") (name "Net-(D_3V3-C)") (class "Default")
      (node (ref "D_3V3") (pin "K") (pinfunction "C_K") (pintype "passive"))
      (node (ref "PR_3.3V") (pin "2") (pinfunction "2_2") (pintype "passive"))
    )
    (net (code "51") (name "Net-(D_5V-C)") (class "Default")
      (node (ref "D_5V") (pin "K") (pinfunction "C_K") (pintype "passive"))
      (node (ref "PR_5V") (pin "2") (pinfunction "2_2") (pintype "passive"))
    )
    (net (code "52") (name "Net-(FTDI-Pad5)") (class "Default")
      (node (ref "FTDI") (pin "5") (pinfunction "5_5") (pintype "passive"))
      (node (ref "RDX") (pin "1") (pinfunction "1_1") (pintype "passive"))
    )
    (net (code "53") (name "Net-(IO_UC-(PCI2{slash}SS{slash}OC1B)PB2)") (class "Default")
      (node (ref "IO_UC") (pin "16") (pinfunction "(PCI2/SS/OC1B)PB2_16") (pintype "bidirectional"))
      (node (ref "R_NI1") (pin "2") (pinfunction "2_2") (pintype "passive"))
    )
    (net (code "54") (name "Net-(IO_UC-PB6(XTAL1{slash}TOSC1{slash}PCI6))") (class "Default")
      (node (ref "C_UXTAL1") (pin "1") (pinfunction "1_1") (pintype "passive"))
      (node (ref "IO_UC") (pin "9") (pinfunction "PB6(XTAL1/TOSC1/PCI6)_9") (pintype "bidirectional"))
      (node (ref "XTALU") (pin "2") (pinfunction "2_2") (pintype "passive"))
    )
    (net (code "55") (name "Net-(IO_UC-PB7(XTAL2{slash}TOSC2{slash}PCI7))") (class "Default")
      (node (ref "C_UXTAL2") (pin "1") (pinfunction "1_1") (pintype "passive"))
      (node (ref "IO_UC") (pin "10") (pinfunction "PB7(XTAL2/TOSC2/PCI7)_10") (pintype "bidirectional"))
      (node (ref "XTALU") (pin "1") (pinfunction "1_1") (pintype "passive"))
    )
    (net (code "56") (name "Net-(J_3V3VB-S)") (class "Default")
      (node (ref "BREAKOUT") (pin "3") (pinfunction "3_3") (pintype "passive"))
      (node (ref "J_3V3V") (pin "2") (pinfunction "S_2") (pintype "passive"))
    )
    (net (code "57") (name "Net-(J_5VB-S)") (class "Default")
      (node (ref "BREAKOUT") (pin "1") (pinfunction "1_1") (pintype "passive"))
      (node (ref "J_5V") (pin "2") (pinfunction "S_2") (pintype "passive"))
    )
    (net (code "58") (name "Net-(LO1-C)") (class "Default")
      (node (ref "LO1") (pin "K") (pinfunction "C_K") (pintype "passive"))
      (node (ref "SSR1") (pin "4") (pinfunction "-_4") (pintype "bidirectional"))
      (node (ref "T1") (pin "C") (pinfunction "C_C") (pintype "passive"))
    )
    (net (code "59") (name "Net-(LO1-PadA)") (class "Default")
      (node (ref "LO1") (pin "A") (pinfunction "A_A") (pintype "passive"))
      (node (ref "RO13") (pin "1") (pinfunction "1_1") (pintype "passive"))
    )
    (net (code "60") (name "Net-(LO2-C)") (class "Default")
      (node (ref "LO2") (pin "K") (pinfunction "C_K") (pintype "passive"))
      (node (ref "SSR2") (pin "4") (pinfunction "-_4") (pintype "bidirectional"))
      (node (ref "T2") (pin "C") (pinfunction "C_C") (pintype "passive"))
    )
    (net (code "61") (name "Net-(LO2-PadA)") (class "Default")
      (node (ref "LO2") (pin "A") (pinfunction "A_A") (pintype "passive"))
      (node (ref "RO23") (pin "1") (pinfunction "1_1") (pintype "passive"))
    )
    (net (code "62") (name "Net-(LO3-C)") (class "Default")
      (node (ref "LO3") (pin "K") (pinfunction "C_K") (pintype "passive"))
      (node (ref "SSR3") (pin "4") (pinfunction "-_4") (pintype "bidirectional"))
      (node (ref "T3") (pin "C") (pinfunction "C_C") (pintype "passive"))
    )
    (net (code "63") (name "Net-(LO3-PadA)") (class "Default")
      (node (ref "LO3") (pin "A") (pinfunction "A_A") (pintype "passive"))
      (node (ref "RO33") (pin "1") (pinfunction "1_1") (pintype "passive"))
    )
    (net (code "64") (name "Net-(LO4-C)") (class "Default")
      (node (ref "LO4") (pin "K") (pinfunction "C_K") (pintype "passive"))
      (node (ref "SSR4") (pin "4") (pinfunction "-_4") (pintype "bidirectional"))
      (node (ref "T4") (pin "C") (pinfunction "C_C") (pintype "passive"))
    )
    (net (code "65") (name "Net-(LO4-PadA)") (class "Default")
      (node (ref "LO4") (pin "A") (pinfunction "A_A") (pintype "passive"))
      (node (ref "RO43") (pin "1") (pinfunction "1_1") (pintype "passive"))
    )
    (net (code "66") (name "Net-(LO5-C)") (class "Default")
      (node (ref "LO5") (pin "K") (pinfunction "C_K") (pintype "passive"))
      (node (ref "SSR5") (pin "4") (pinfunction "-_4") (pintype "bidirectional"))
      (node (ref "T5") (pin "C") (pinfunction "C_C") (pintype "passive"))
    )
    (net (code "67") (name "Net-(LO5-PadA)") (class "Default")
      (node (ref "LO5") (pin "A") (pinfunction "A_A") (pintype "passive"))
      (node (ref "RO53") (pin "1") (pinfunction "1_1") (pintype "passive"))
    )
    (net (code "68") (name "Net-(LO6-C)") (class "Default")
      (node (ref "LO6") (pin "K") (pinfunction "C_K") (pintype "passive"))
      (node (ref "SSR6") (pin "4") (pinfunction "-_4") (pintype "bidirectional"))
      (node (ref "T6") (pin "C") (pinfunction "C_C") (pintype "passive"))
    )
    (net (code "69") (name "Net-(LO6-PadA)") (class "Default")
      (node (ref "LO6") (pin "A") (pinfunction "A_A") (pintype "passive"))
      (node (ref "RO63") (pin "1") (pinfunction "1_1") (pintype "passive"))
    )
    (net (code "70") (name "Net-(LO7-C)") (class "Default")
      (node (ref "LO7") (pin "K") (pinfunction "C_K") (pintype "passive"))
      (node (ref "SSR7") (pin "4") (pinfunction "-_4") (pintype "bidirectional"))
      (node (ref "T7") (pin "C") (pinfunction "C_C") (pintype "passive"))
    )
    (net (code "71") (name "Net-(LO7-PadA)") (class "Default")
      (node (ref "LO7") (pin "A") (pinfunction "A_A") (pintype "passive"))
      (node (ref "RO73") (pin "1") (pinfunction "1_1") (pintype "passive"))
    )
    (net (code "72") (name "Net-(LO8-C)") (class "Default")
      (node (ref "LO8") (pin "K") (pinfunction "C_K") (pintype "passive"))
      (node (ref "SSR8") (pin "4") (pinfunction "-_4") (pintype "bidirectional"))
      (node (ref "T8") (pin "C") (pinfunction "C_C") (pintype "passive"))
    )
    (net (code "73") (name "Net-(LO8-PadA)") (class "Default")
      (node (ref "LO8") (pin "A") (pinfunction "A_A") (pintype "passive"))
      (node (ref "RO83") (pin "1") (pinfunction "1_1") (pintype "passive"))
    )
    (net (code "74") (name "Net-(PSUA-KL)") (class "Default")
      (node (ref "D_PSU") (pin "A") (pinfunction "A_A") (pintype "passive"))
      (node (ref "PSU") (pin "1") (pinfunction "KL_1") (pintype "passive"))
    )
    (net (code "75") (name "Net-(REG_3V3-IN)") (class "Default")
      (node (ref "CP01") (pin "+") (pinfunction "+_+") (pintype "passive"))
      (node (ref "D_PSU") (pin "C") (pinfunction "C_C") (pintype "passive"))
      (node (ref "D_PSU1") (pin "C") (pinfunction "C_C") (pintype "passive"))
      (node (ref "D_PSU2") (pin "C") (pinfunction "C_C") (pintype "passive"))
      (node (ref "REG_3V3") (pin "3") (pinfunction "IN_3") (pintype "input"))
      (node (ref "REG_5V") (pin "3") (pinfunction "IN_3") (pintype "input"))
    )
    (net (code "76") (name "Net-(RO12-Pad1)") (class "Default")
      (node (ref "RO12") (pin "1") (pinfunction "1_1") (pintype "passive"))
      (node (ref "T1") (pin "B") (pinfunction "B_B") (pintype "passive"))
    )
    (net (code "77") (name "Net-(RO22-Pad1)") (class "Default")
      (node (ref "RO22") (pin "1") (pinfunction "1_1") (pintype "passive"))
      (node (ref "T2") (pin "B") (pinfunction "B_B") (pintype "passive"))
    )
    (net (code "78") (name "Net-(RO32-Pad1)") (class "Default")
      (node (ref "RO32") (pin "1") (pinfunction "1_1") (pintype "passive"))
      (node (ref "T3") (pin "B") (pinfunction "B_B") (pintype "passive"))
    )
    (net (code "79") (name "Net-(RO42-Pad1)") (class "Default")
      (node (ref "RO42") (pin "1") (pinfunction "1_1") (pintype "passive"))
      (node (ref "T4") (pin "B") (pinfunction "B_B") (pintype "passive"))
    )
    (net (code "80") (name "Net-(RO52-Pad1)") (class "Default")
      (node (ref "RO52") (pin "1") (pinfunction "1_1") (pintype "passive"))
      (node (ref "T5") (pin "B") (pinfunction "B_B") (pintype "passive"))
    )
    (net (code "81") (name "Net-(RO62-Pad1)") (class "Default")
      (node (ref "RO62") (pin "1") (pinfunction "1_1") (pintype "passive"))
      (node (ref "T6") (pin "B") (pinfunction "B_B") (pintype "passive"))
    )
    (net (code "82") (name "Net-(RO72-Pad1)") (class "Default")
      (node (ref "RO72") (pin "1") (pinfunction "1_1") (pintype "passive"))
      (node (ref "T7") (pin "B") (pinfunction "B_B") (pintype "passive"))
    )
    (net (code "83") (name "Net-(RO82-Pad1)") (class "Default")
      (node (ref "RO82") (pin "1") (pinfunction "1_1") (pintype "passive"))
      (node (ref "T8") (pin "B") (pinfunction "B_B") (pintype "passive"))
    )
    (net (code "84") (name "Net-(SSR1-L2)") (class "Default")
      (node (ref "FUSE1") (pin "1") (pinfunction "1_1") (pintype "passive"))
      (node (ref "SSR1") (pin "2") (pinfunction "L2_2") (pintype "bidirectional"))
    )
    (net (code "85") (name "Net-(SSR2-L2)") (class "Default")
      (node (ref "FUSE2") (pin "1") (pinfunction "1_1") (pintype "passive"))
      (node (ref "SSR2") (pin "2") (pinfunction "L2_2") (pintype "bidirectional"))
    )
    (net (code "86") (name "Net-(SSR3-L2)") (class "Default")
      (node (ref "FUSE3") (pin "1") (pinfunction "1_1") (pintype "passive"))
      (node (ref "SSR3") (pin "2") (pinfunction "L2_2") (pintype "bidirectional"))
    )
    (net (code "87") (name "Net-(SSR4-L2)") (class "Default")
      (node (ref "FUSE4") (pin "1") (pinfunction "1_1") (pintype "passive"))
      (node (ref "SSR4") (pin "2") (pinfunction "L2_2") (pintype "bidirectional"))
    )
    (net (code "88") (name "Net-(SSR5-L2)") (class "Default")
      (node (ref "FUSE5") (pin "1") (pinfunction "1_1") (pintype "passive"))
      (node (ref "SSR5") (pin "2") (pinfunction "L2_2") (pintype "bidirectional"))
    )
    (net (code "89") (name "Net-(SSR6-L2)") (class "Default")
      (node (ref "FUSE6") (pin "1") (pinfunction "1_1") (pintype "passive"))
      (node (ref "SSR6") (pin "2") (pinfunction "L2_2") (pintype "bidirectional"))
    )
    (net (code "90") (name "Net-(SSR7-L2)") (class "Default")
      (node (ref "FUSE7") (pin "1") (pinfunction "1_1") (pintype "passive"))
      (node (ref "SSR7") (pin "2") (pinfunction "L2_2") (pintype "bidirectional"))
    )
    (net (code "91") (name "Net-(SSR8-L2)") (class "Default")
      (node (ref "FUSE8") (pin "1") (pinfunction "1_1") (pintype "passive"))
      (node (ref "SSR8") (pin "2") (pinfunction "L2_2") (pintype "bidirectional"))
    )
    (net (code "92") (name "unconnected-(U$4-Pad5V)") (class "Default")
      (node (ref "U$4") (pin "5V") (pinfunction "5V_5V") (pintype "bidirectional"))
    )
    (net (code "93") (name "unconnected-(U$4-PadKEY)") (class "Default")
      (node (ref "U$4") (pin "KEY") (pinfunction "KEY_KEY") (pintype "bidirectional"))
    )
    (net (code "94") (name "unconnected-(U$6-Pad32K)") (class "Default")
      (node (ref "U$6") (pin "32K") (pinfunction "32K_32K") (pintype "bidirectional"))
    )
    (net (code "95") (name "unconnected-(U$6-PadBAT)") (class "Default")
      (node (ref "U$6") (pin "BAT") (pinfunction "BAT_BAT") (pintype "bidirectional"))
    )
    (net (code "96") (name "unconnected-(U$6-PadRST)") (class "Default")
      (node (ref "U$6") (pin "RST") (pinfunction "RST_RST") (pintype "bidirectional"))
    )
    (net (code "97") (name "unconnected-(U$6-PadSQW)") (class "Default")
      (node (ref "U$6") (pin "SQW") (pinfunction "SQW_SQW") (pintype "bidirectional"))
    )
  )
)
